# Lights_Tester.net
KiCad netlist of a schematic drawn in Altium Designer
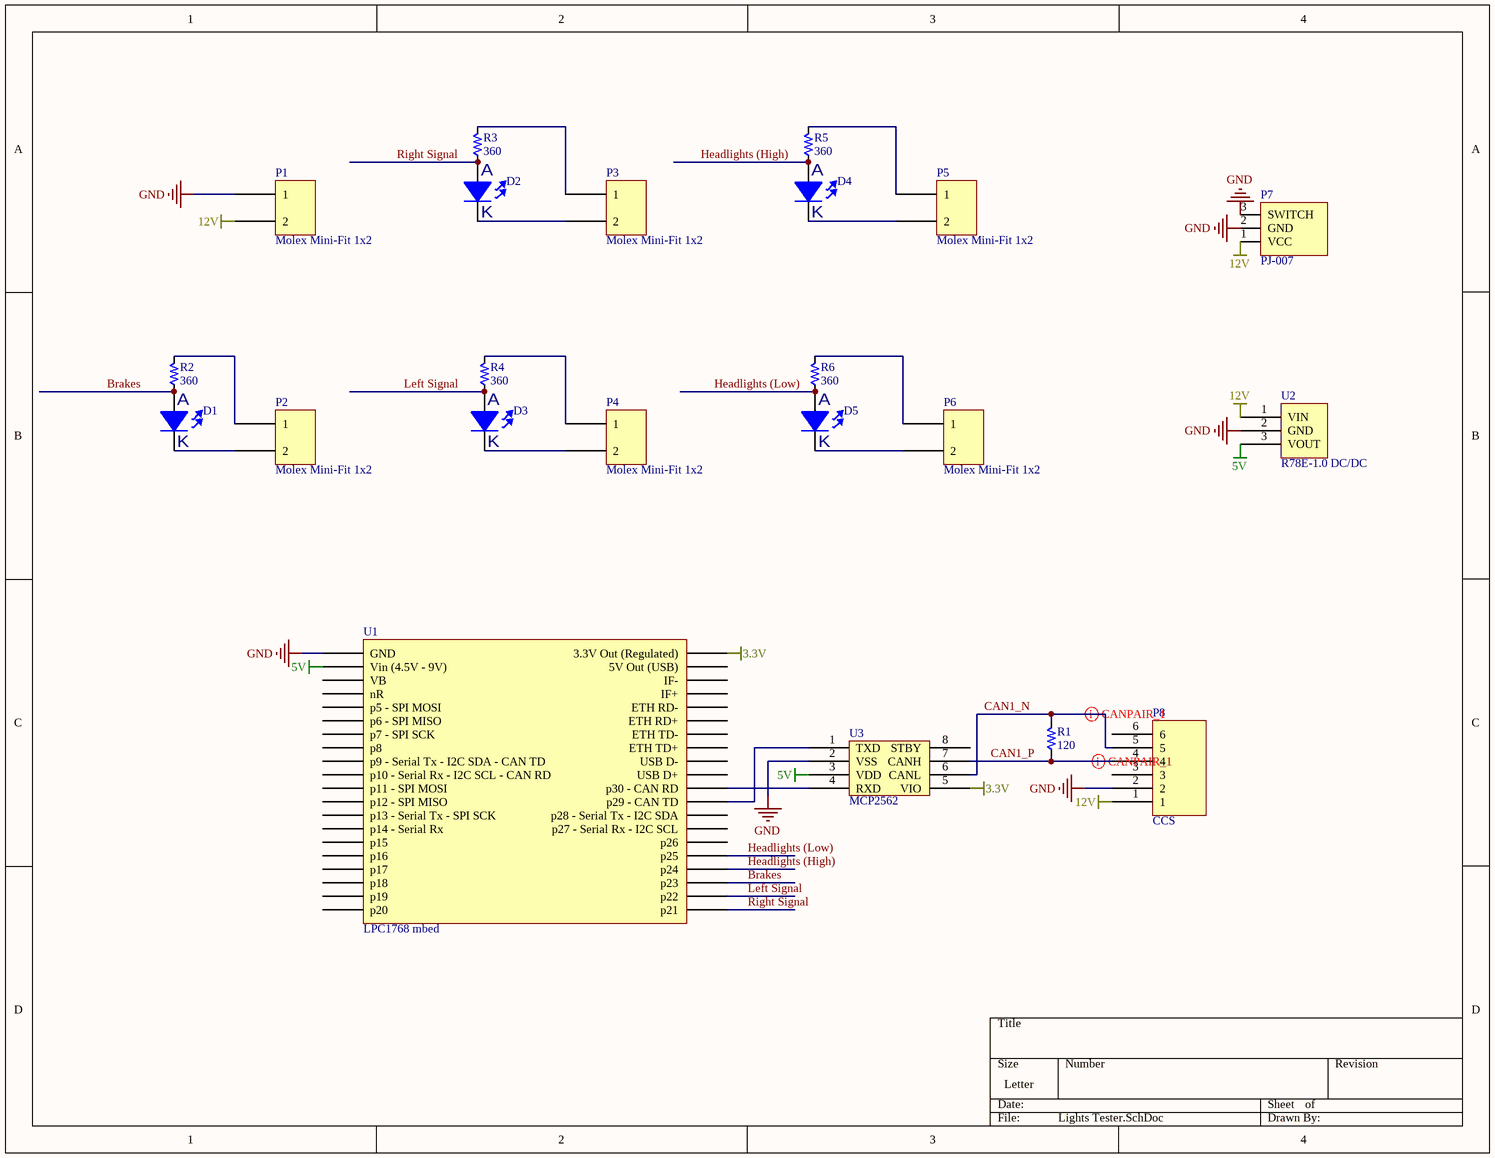
[diagram p0: Lights Tester.SchDoc]

(export (version "E")
  (design (tool "Eeschema 10.0.6"))
  (components
    (comp (ref "D1")
      (value "LED RED")
      (footprint "RED LED")
      (libsource (lib "LED RED 150141RS73100") (part "LED RED"))
    )
    (comp (ref "D2")
      (value "LED RED")
      (footprint "RED LED")
      (libsource (lib "LED RED 150141RS73100") (part "LED RED"))
    )
    (comp (ref "D3")
      (value "LED RED")
      (footprint "RED LED")
      (libsource (lib "LED RED 150141RS73100") (part "LED RED"))
    )
    (comp (ref "D4")
      (value "LED RED")
      (footprint "RED LED")
      (libsource (lib "LED RED 150141RS73100") (part "LED RED"))
    )
    (comp (ref "D5")
      (value "LED RED")
      (footprint "RED LED")
      (libsource (lib "LED RED 150141RS73100") (part "LED RED"))
    )
    (comp (ref "P1")
      (value "Molex Mini-Fit 1x2")
      (footprint "Molex Mini-Fit Jr 2x1")
      (libsource (lib "Molex Mini-Fit Jr 1x2") (part "Molex Mini-Fit 1x2"))
    )
    (comp (ref "P2")
      (value "Molex Mini-Fit 1x2")
      (footprint "Molex Mini-Fit Jr 2x1")
      (libsource (lib "Molex Mini-Fit Jr 1x2") (part "Molex Mini-Fit 1x2"))
    )
    (comp (ref "P3")
      (value "Molex Mini-Fit 1x2")
      (footprint "Molex Mini-Fit Jr 2x1")
      (libsource (lib "Molex Mini-Fit Jr 1x2") (part "Molex Mini-Fit 1x2"))
    )
    (comp (ref "P4")
      (value "Molex Mini-Fit 1x2")
      (footprint "Molex Mini-Fit Jr 2x1")
      (libsource (lib "Molex Mini-Fit Jr 1x2") (part "Molex Mini-Fit 1x2"))
    )
    (comp (ref "P5")
      (value "Molex Mini-Fit 1x2")
      (footprint "Molex Mini-Fit Jr 2x1")
      (libsource (lib "Molex Mini-Fit Jr 1x2") (part "Molex Mini-Fit 1x2"))
    )
    (comp (ref "P6")
      (value "Molex Mini-Fit 1x2")
      (footprint "Molex Mini-Fit Jr 2x1")
      (libsource (lib "Molex Mini-Fit Jr 1x2") (part "Molex Mini-Fit 1x2"))
    )
    (comp (ref "P7")
      (value "PJ-007")
      (footprint "BARREL JACK PJ007")
      (libsource (lib "BARREL JACK PJ-007") (part "Component_1"))
    )
    (comp (ref "P8")
      (value "CCS")
      (footprint "PCB_MLX_MICROFIT_3X2")
      (libsource (lib "SCH_MLX_MICROFIT_3X2_P") (part "SCH_MLX_MICROFIT_3X2"))
    )
    (comp (ref "R1")
      (value "120")
      (footprint "PCB_GENERIC_SMD_0603")
      (description "120 Ohms")
      (libsource (lib "SCH_GENERIC_RESISTOR_0603") (part "SCH_GENERIC_RESISTOR_0603"))
    )
    (comp (ref "R2")
      (value "SCH_GENERIC_RESISTOR_0603")
      (footprint "PCB_GENERIC_SMD_0603")
      (description "Generic SMD resistor 0603")
      (fields (field (name "RESISTANCE") "360"))
      (libsource (lib "SCH_GENERIC_RESISTOR_0603") (part "SCH_GENERIC_RESISTOR_0603"))
    )
    (comp (ref "R3")
      (value "SCH_GENERIC_RESISTOR_0603")
      (footprint "PCB_GENERIC_SMD_0603")
      (description "Generic SMD resistor 0603")
      (fields (field (name "RESISTANCE") "360"))
      (libsource (lib "SCH_GENERIC_RESISTOR_0603") (part "SCH_GENERIC_RESISTOR_0603"))
    )
    (comp (ref "R4")
      (value "SCH_GENERIC_RESISTOR_0603")
      (footprint "PCB_GENERIC_SMD_0603")
      (description "Generic SMD resistor 0603")
      (fields (field (name "RESISTANCE") "360"))
      (libsource (lib "SCH_GENERIC_RESISTOR_0603") (part "SCH_GENERIC_RESISTOR_0603"))
    )
    (comp (ref "R5")
      (value "SCH_GENERIC_RESISTOR_0603")
      (footprint "PCB_GENERIC_SMD_0603")
      (description "Generic SMD resistor 0603")
      (fields (field (name "RESISTANCE") "360"))
      (libsource (lib "SCH_GENERIC_RESISTOR_0603") (part "SCH_GENERIC_RESISTOR_0603"))
    )
    (comp (ref "R6")
      (value "SCH_GENERIC_RESISTOR_0603")
      (footprint "PCB_GENERIC_SMD_0603")
      (description "Generic SMD resistor 0603")
      (fields (field (name "RESISTANCE") "360"))
      (libsource (lib "SCH_GENERIC_RESISTOR_0603") (part "SCH_GENERIC_RESISTOR_0603"))
    )
    (comp (ref "U1")
      (value "LPC1768 mbed")
      (footprint "LPC 1768 mbed Layout")
      (libsource (lib "LPC1768_mbed_SCH") (part "LPC1768 mbed"))
    )
    (comp (ref "U2")
      (value "R78E-1.0 DC/DC")
      (footprint "R78-1.0")
      (libsource (lib "R78E-1.0_DCDC_SCH") (part "R78E-1.0"))
    )
    (comp (ref "U3") (value "MCP2562") (footprint "MCP2562") (libsource (lib "MCP2562_SCH") (part "MCP2562")))
  )
  (nets
    (net (code "1") (name "/Brakes") (class "Default")
      (node (ref "D1") (pin "2") (pintype "passive"))
      (node (ref "R2") (pin "1") (pinfunction "1_1") (pintype "passive"))
      (node (ref "U1") (pin "23") (pinfunction "p23_23") (pintype "passive"))
    )
    (net (code "2") (name "/CAN1_N") (class "Default")
      (node (ref "P8") (pin "5") (pinfunction "5_5") (pintype "passive"))
      (node (ref "R1") (pin "2") (pinfunction "2_2") (pintype "passive"))
      (node (ref "U3") (pin "6") (pinfunction "CANL_6") (pintype "passive"))
    )
    (net (code "3") (name "/CAN1_P") (class "Default")
      (node (ref "P8") (pin "4") (pinfunction "4_4") (pintype "passive"))
      (node (ref "R1") (pin "1") (pinfunction "1_1") (pintype "passive"))
      (node (ref "U3") (pin "7") (pinfunction "CANH_7") (pintype "passive"))
    )
    (net (code "4") (name "/Headlights (High)") (class "Default")
      (node (ref "D4") (pin "2") (pintype "passive"))
      (node (ref "R5") (pin "1") (pinfunction "1_1") (pintype "passive"))
      (node (ref "U1") (pin "24") (pinfunction "p24_24") (pintype "passive"))
    )
    (net (code "5") (name "/Headlights (Low)") (class "Default")
      (node (ref "D5") (pin "2") (pintype "passive"))
      (node (ref "R6") (pin "1") (pinfunction "1_1") (pintype "passive"))
      (node (ref "U1") (pin "25") (pinfunction "p25_25") (pintype "passive"))
    )
    (net (code "6") (name "/Left Signal") (class "Default")
      (node (ref "D3") (pin "2") (pintype "passive"))
      (node (ref "R4") (pin "1") (pinfunction "1_1") (pintype "passive"))
      (node (ref "U1") (pin "22") (pinfunction "p22_22") (pintype "passive"))
    )
    (net (code "7") (name "/Right Signal") (class "Default")
      (node (ref "D2") (pin "2") (pintype "passive"))
      (node (ref "R3") (pin "1") (pinfunction "1_1") (pintype "passive"))
      (node (ref "U1") (pin "21") (pinfunction "p21_21") (pintype "passive"))
    )
    (net (code "8") (name "3.3V") (class "Default")
      (node (ref "U1") (pin "40") (pinfunction "3.3V_Out_(Regulated)_40") (pintype "passive"))
      (node (ref "U3") (pin "5") (pinfunction "VIO_5") (pintype "passive"))
    )
    (net (code "9") (name "5V") (class "Default")
      (node (ref "U1") (pin "2") (pinfunction "Vin_(4.5V_-_9V)_2") (pintype "passive"))
      (node (ref "U2") (pin "3") (pinfunction "VOUT_3") (pintype "passive"))
      (node (ref "U3") (pin "3") (pinfunction "VDD_3") (pintype "passive"))
    )
    (net (code "10") (name "12V") (class "Default")
      (node (ref "P1") (pin "2") (pinfunction "2_2") (pintype "passive"))
      (node (ref "P7") (pin "1") (pinfunction "VCC_1") (pintype "passive"))
      (node (ref "P8") (pin "1") (pinfunction "1_1") (pintype "passive"))
      (node (ref "U2") (pin "1") (pinfunction "VIN_1") (pintype "passive"))
    )
    (net (code "11") (name "GND") (class "Default")
      (node (ref "P1") (pin "1") (pinfunction "1_1") (pintype "passive"))
      (node (ref "P7") (pin "2") (pinfunction "GND_2") (pintype "passive"))
      (node (ref "P7") (pin "3") (pinfunction "SWITCH_3") (pintype "passive"))
      (node (ref "P8") (pin "2") (pinfunction "2_2") (pintype "passive"))
      (node (ref "U1") (pin "1") (pinfunction "GND_1") (pintype "passive"))
      (node (ref "U2") (pin "2") (pinfunction "GND_2") (pintype "passive"))
      (node (ref "U3") (pin "2") (pinfunction "VSS_2") (pintype "passive"))
    )
    (net (code "12") (name "Net-(D1-Pad1)") (class "Default")
      (node (ref "D1") (pin "1") (pintype "passive"))
      (node (ref "P2") (pin "2") (pinfunction "2_2") (pintype "passive"))
    )
    (net (code "13") (name "Net-(D2-Pad1)") (class "Default")
      (node (ref "D2") (pin "1") (pintype "passive"))
      (node (ref "P3") (pin "2") (pinfunction "2_2") (pintype "passive"))
    )
    (net (code "14") (name "Net-(D3-Pad1)") (class "Default")
      (node (ref "D3") (pin "1") (pintype "passive"))
      (node (ref "P4") (pin "2") (pinfunction "2_2") (pintype "passive"))
    )
    (net (code "15") (name "Net-(D4-Pad1)") (class "Default")
      (node (ref "D4") (pin "1") (pintype "passive"))
      (node (ref "P5") (pin "2") (pinfunction "2_2") (pintype "passive"))
    )
    (net (code "16") (name "Net-(D5-Pad1)") (class "Default")
      (node (ref "D5") (pin "1") (pintype "passive"))
      (node (ref "P6") (pin "2") (pinfunction "2_2") (pintype "passive"))
    )
    (net (code "17") (name "Net-(P2-Pad1)") (class "Default")
      (node (ref "P2") (pin "1") (pinfunction "1_1") (pintype "passive"))
      (node (ref "R2") (pin "2") (pinfunction "2_2") (pintype "passive"))
    )
    (net (code "18") (name "Net-(P3-Pad1)") (class "Default")
      (node (ref "P3") (pin "1") (pinfunction "1_1") (pintype "passive"))
      (node (ref "R3") (pin "2") (pinfunction "2_2") (pintype "passive"))
    )
    (net (code "19") (name "Net-(P4-Pad1)") (class "Default")
      (node (ref "P4") (pin "1") (pinfunction "1_1") (pintype "passive"))
      (node (ref "R4") (pin "2") (pinfunction "2_2") (pintype "passive"))
    )
    (net (code "20") (name "Net-(P5-Pad1)") (class "Default")
      (node (ref "P5") (pin "1") (pinfunction "1_1") (pintype "passive"))
      (node (ref "R5") (pin "2") (pinfunction "2_2") (pintype "passive"))
    )
    (net (code "21") (name "Net-(P6-Pad1)") (class "Default")
      (node (ref "P6") (pin "1") (pinfunction "1_1") (pintype "passive"))
      (node (ref "R6") (pin "2") (pinfunction "2_2") (pintype "passive"))
    )
    (net (code "22") (name "Net-(U1-p29_-_CAN_TD)") (class "Default")
      (node (ref "U1") (pin "29") (pinfunction "p29_-_CAN_TD_29") (pintype "passive"))
      (node (ref "U3") (pin "1") (pinfunction "TXD_1") (pintype "passive"))
    )
    (net (code "23") (name "Net-(U1-p30_-_CAN_RD)") (class "Default")
      (node (ref "U1") (pin "30") (pinfunction "p30_-_CAN_RD_30") (pintype "passive"))
      (node (ref "U3") (pin "4") (pinfunction "RXD_4") (pintype "passive"))
    )
    (net (code "24") (name "unconnected-(P8-Pad3)") (class "Default")
      (node (ref "P8") (pin "3") (pinfunction "3_3") (pintype "passive"))
    )
    (net (code "25") (name "unconnected-(P8-Pad6)") (class "Default")
      (node (ref "P8") (pin "6") (pinfunction "6_6") (pintype "passive"))
    )
    (net (code "26") (name "unconnected-(U1-5V_Out_(USB)-Pad39)") (class "Default")
      (node (ref "U1") (pin "39") (pinfunction "5V_Out_(USB)_39") (pintype "passive"))
    )
    (net (code "27") (name "unconnected-(U1-ETH_RD+-Pad35)") (class "Default")
      (node (ref "U1") (pin "35") (pinfunction "ETH_RD+_35") (pintype "passive"))
    )
    (net (code "28") (name "unconnected-(U1-ETH_RD--Pad36)") (class "Default")
      (node (ref "U1") (pin "36") (pinfunction "ETH_RD-_36") (pintype "passive"))
    )
    (net (code "29") (name "unconnected-(U1-ETH_TD+-Pad33)") (class "Default")
      (node (ref "U1") (pin "33") (pinfunction "ETH_TD+_33") (pintype "passive"))
    )
    (net (code "30") (name "unconnected-(U1-ETH_TD--Pad34)") (class "Default")
      (node (ref "U1") (pin "34") (pinfunction "ETH_TD-_34") (pintype "passive"))
    )
    (net (code "31") (name "unconnected-(U1-IF+-Pad37)") (class "Default")
      (node (ref "U1") (pin "37") (pinfunction "IF+_37") (pintype "passive"))
    )
    (net (code "32") (name "unconnected-(U1-IF--Pad38)") (class "Default")
      (node (ref "U1") (pin "38") (pinfunction "IF-_38") (pintype "passive"))
    )
    (net (code "33") (name "unconnected-(U1-USB_D+-Pad31)") (class "Default")
      (node (ref "U1") (pin "31") (pinfunction "USB_D+_31") (pintype "passive"))
    )
    (net (code "34") (name "unconnected-(U1-USB_D--Pad32)") (class "Default")
      (node (ref "U1") (pin "32") (pinfunction "USB_D-_32") (pintype "passive"))
    )
    (net (code "35") (name "unconnected-(U1-VB-Pad3)") (class "Default")
      (node (ref "U1") (pin "3") (pinfunction "VB_3") (pintype "passive"))
    )
    (net (code "36") (name "unconnected-(U1-nR-Pad4)") (class "Default")
      (node (ref "U1") (pin "4") (pinfunction "nR_4") (pintype "passive"))
    )
    (net (code "37") (name "unconnected-(U1-p5_-_SPI_MOSI-Pad5)") (class "Default")
      (node (ref "U1") (pin "5") (pinfunction "p5_-_SPI_MOSI_5") (pintype "passive"))
    )
    (net (code "38") (name "unconnected-(U1-p6_-_SPI_MISO-Pad6)") (class "Default")
      (node (ref "U1") (pin "6") (pinfunction "p6_-_SPI_MISO_6") (pintype "passive"))
    )
    (net (code "39") (name "unconnected-(U1-p7_-_SPI_SCK-Pad7)") (class "Default")
      (node (ref "U1") (pin "7") (pinfunction "p7_-_SPI_SCK_7") (pintype "passive"))
    )
    (net (code "40") (name "unconnected-(U1-p8-Pad8)") (class "Default")
      (node (ref "U1") (pin "8") (pinfunction "p8_8") (pintype "passive"))
    )
    (net (code "41") (name "unconnected-(U1-p9_-_Serial_Tx_-_I2C_SDA_-_CAN_TD-Pad9)") (class "Default")
      (node (ref "U1") (pin "9") (pinfunction "p9_-_Serial_Tx_-_I2C_SDA_-_CAN_TD_9") (pintype "passive"))
    )
    (net (code "42") (name "unconnected-(U1-p10_-_Serial_Rx_-_I2C_SCL_-_CAN_RD-Pad10)") (class "Default")
      (node (ref "U1") (pin "10") (pinfunction "p10_-_Serial_Rx_-_I2C_SCL_-_CAN_RD_10") (pintype "passive"))
    )
    (net (code "43") (name "unconnected-(U1-p11_-_SPI_MOSI-Pad11)") (class "Default")
      (node (ref "U1") (pin "11") (pinfunction "p11_-_SPI_MOSI_11") (pintype "passive"))
    )
    (net (code "44") (name "unconnected-(U1-p12_-_SPI_MISO-Pad12)") (class "Default")
      (node (ref "U1") (pin "12") (pinfunction "p12_-_SPI_MISO_12") (pintype "passive"))
    )
    (net (code "45") (name "unconnected-(U1-p13_-_Serial_Tx_-_SPI_SCK-Pad13)") (class "Default")
      (node (ref "U1") (pin "13") (pinfunction "p13_-_Serial_Tx_-_SPI_SCK_13") (pintype "passive"))
    )
    (net (code "46") (name "unconnected-(U1-p14_-_Serial_Rx-Pad14)") (class "Default")
      (node (ref "U1") (pin "14") (pinfunction "p14_-_Serial_Rx_14") (pintype "passive"))
    )
    (net (code "47") (name "unconnected-(U1-p15-Pad15)") (class "Default")
      (node (ref "U1") (pin "15") (pinfunction "p15_15") (pintype "passive"))
    )
    (net (code "48") (name "unconnected-(U1-p16-Pad16)") (class "Default")
      (node (ref "U1") (pin "16") (pinfunction "p16_16") (pintype "passive"))
    )
    (net (code "49") (name "unconnected-(U1-p17-Pad17)") (class "Default")
      (node (ref "U1") (pin "17") (pinfunction "p17_17") (pintype "passive"))
    )
    (net (code "50") (name "unconnected-(U1-p18-Pad18)") (class "Default")
      (node (ref "U1") (pin "18") (pinfunction "p18_18") (pintype "passive"))
    )
    (net (code "51") (name "unconnected-(U1-p19-Pad19)") (class "Default")
      (node (ref "U1") (pin "19") (pinfunction "p19_19") (pintype "passive"))
    )
    (net (code "52") (name "unconnected-(U1-p20-Pad20)") (class "Default")
      (node (ref "U1") (pin "20") (pinfunction "p20_20") (pintype "passive"))
    )
    (net (code "53") (name "unconnected-(U1-p26-Pad26)") (class "Default")
      (node (ref "U1") (pin "26") (pinfunction "p26_26") (pintype "passive"))
    )
    (net (code "54") (name "unconnected-(U1-p27_-_Serial_Rx_-_I2C_SCL-Pad27)") (class "Default")
      (node (ref "U1") (pin "27") (pinfunction "p27_-_Serial_Rx_-_I2C_SCL_27") (pintype "passive"))
    )
    (net (code "55") (name "unconnected-(U1-p28_-_Serial_Tx_-_I2C_SDA-Pad28)") (class "Default")
      (node (ref "U1") (pin "28") (pinfunction "p28_-_Serial_Tx_-_I2C_SDA_28") (pintype "passive"))
    )
    (net (code "56") (name "unconnected-(U3-STBY-Pad8)") (class "Default")
      (node (ref "U3") (pin "8") (pinfunction "STBY_8") (pintype "passive"))
    )
  )
)
